# picoclick_c3_v1_1.net
KiCad netlist of a schematic drawn in EAGLE
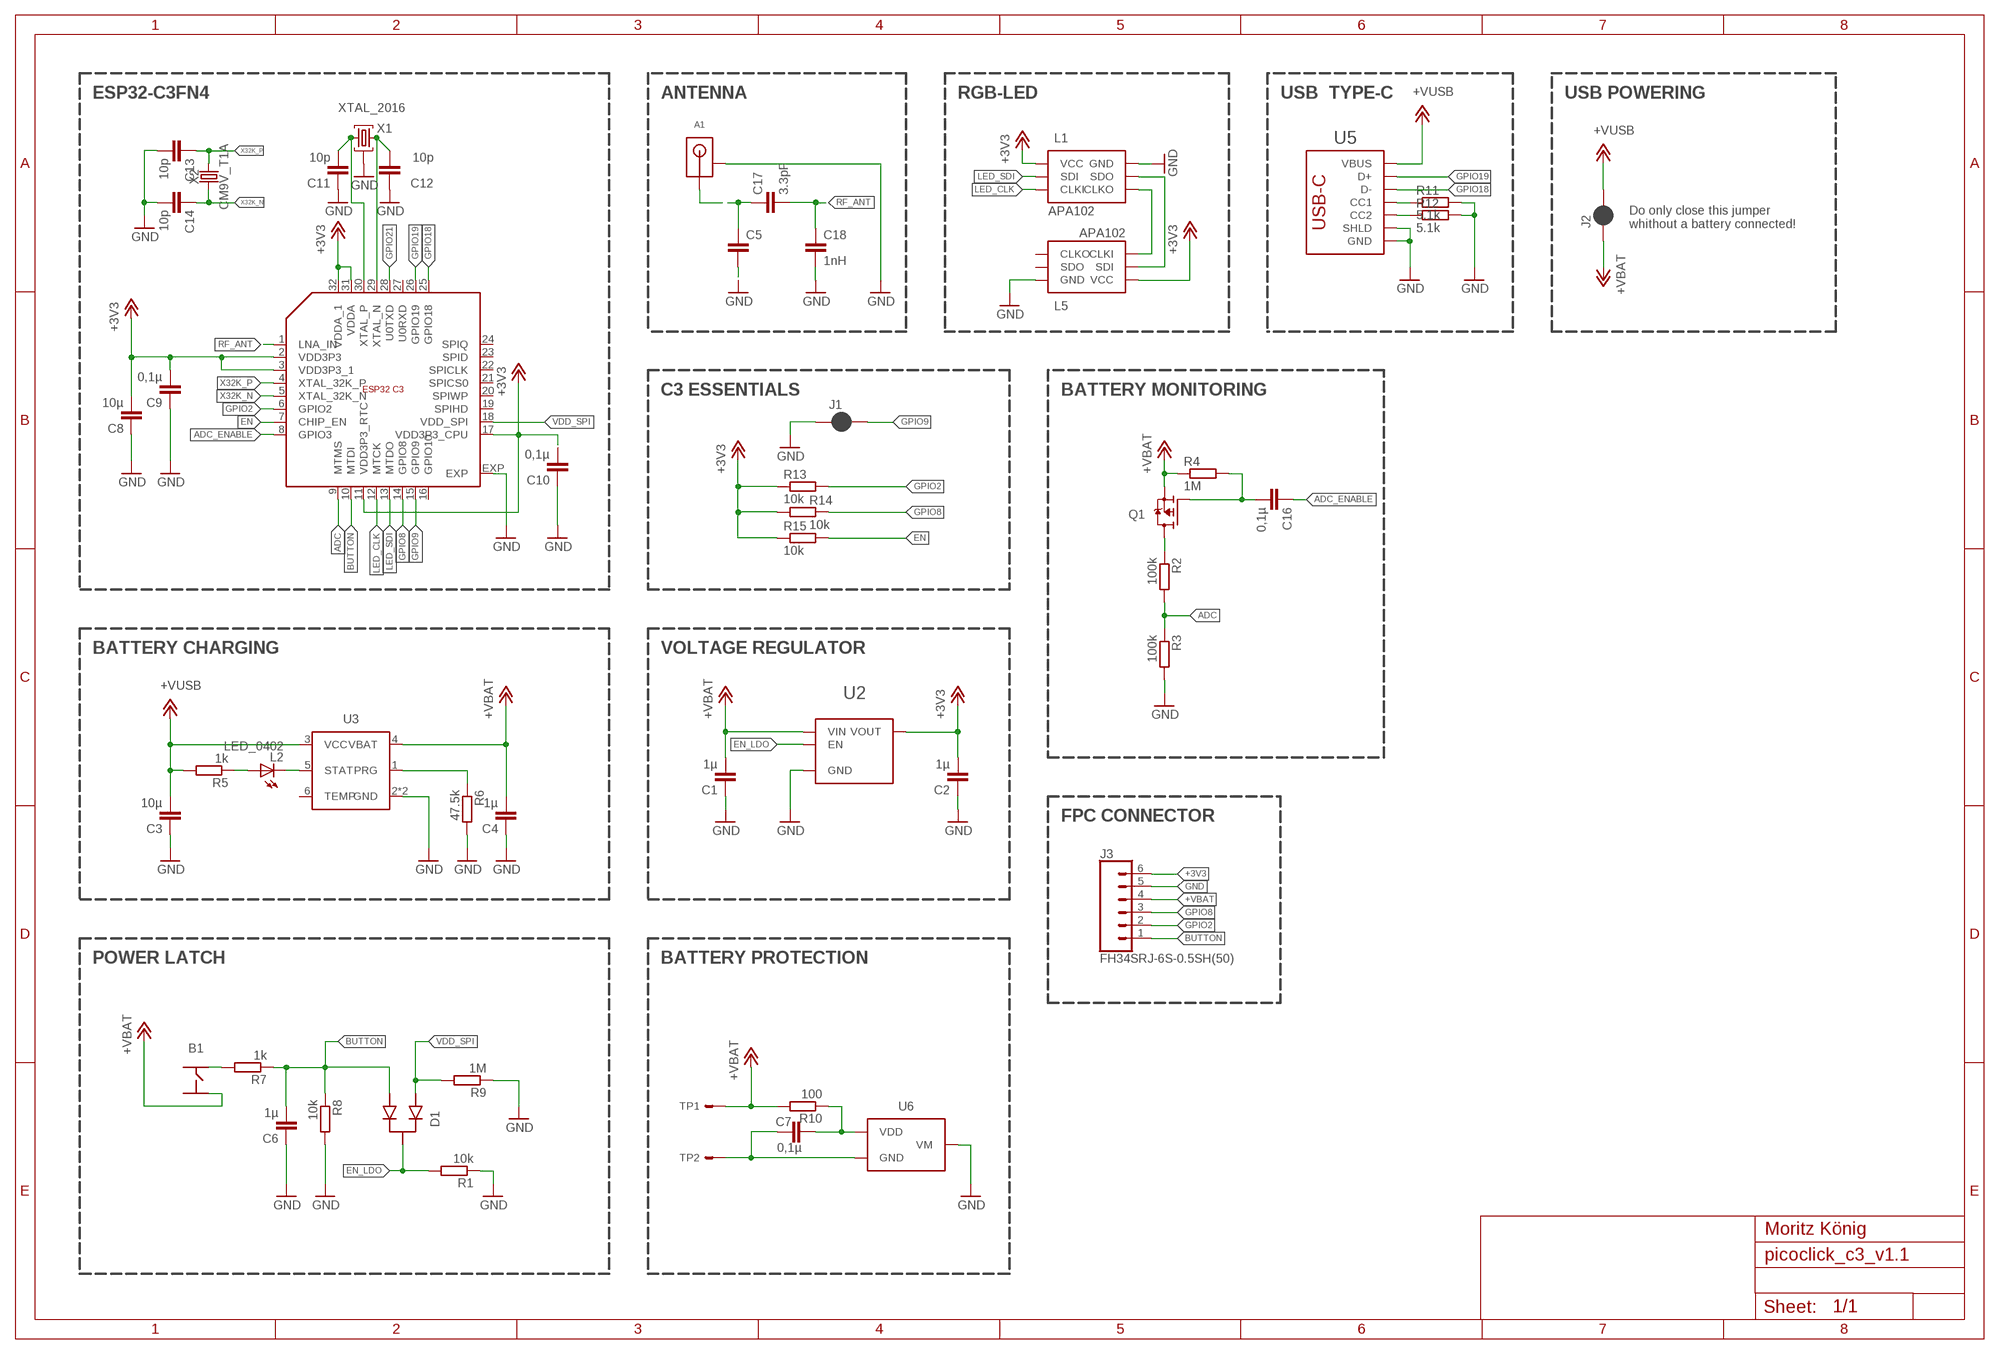
[diagram p0: schematic, sheet 1]

(export (version "E")
  (design (tool "Eeschema 10.0.6"))
  (components
    (comp (ref "A1")
      (value "RFECA3216060A1T_NEW3_M")
      (footprint "eagle-import:RFECA3216060A1T_NEW3_M")
      (libsource (lib "eagle-import") (part "RFECA3216060A1T_NEW3_M"))
    )
    (comp (ref "B1")
      (value "BUTTON_4PIN")
      (footprint "eagle-import:BUTTON_SMD_12MM")
      (libsource (lib "eagle-import") (part "BUTTON_4PIN"))
    )
    (comp (ref "C1")
      (value "1µ")
      (footprint "eagle-import:C0402_S")
      (libsource (lib "eagle-import") (part "C0402_S"))
    )
    (comp (ref "C2")
      (value "1µ")
      (footprint "eagle-import:C0402_S")
      (libsource (lib "eagle-import") (part "C0402_S"))
    )
    (comp (ref "C3")
      (value "10µ")
      (footprint "eagle-import:C0402_S")
      (libsource (lib "eagle-import") (part "C0402_S"))
    )
    (comp (ref "C4")
      (value "1µ")
      (footprint "eagle-import:C0402_S")
      (libsource (lib "eagle-import") (part "C0402_S"))
    )
    (comp (ref "C5")
      (value "C0402_S")
      (footprint "eagle-import:C0402_S")
      (libsource (lib "eagle-import") (part "C0402_S"))
    )
    (comp (ref "C6")
      (value "1µ")
      (footprint "eagle-import:C0402_S")
      (libsource (lib "eagle-import") (part "C0402_S"))
    )
    (comp (ref "C7")
      (value "0,1µ")
      (footprint "eagle-import:C0402_S")
      (libsource (lib "eagle-import") (part "C-EU-0402-WOKEEPOUT_S"))
    )
    (comp (ref "C8")
      (value "10µ")
      (footprint "eagle-import:C0402_S")
      (libsource (lib "eagle-import") (part "C0402_S"))
    )
    (comp (ref "C9")
      (value "0,1µ")
      (footprint "eagle-import:C0402_S")
      (libsource (lib "eagle-import") (part "C0402_S"))
    )
    (comp (ref "C10")
      (value "0,1µ")
      (footprint "eagle-import:C0402_S")
      (libsource (lib "eagle-import") (part "C0402_S"))
    )
    (comp (ref "C11")
      (value "10p")
      (footprint "eagle-import:C0402_S")
      (libsource (lib "eagle-import") (part "C0402_S"))
    )
    (comp (ref "C12")
      (value "10p")
      (footprint "eagle-import:C0402_S")
      (libsource (lib "eagle-import") (part "C0402_S"))
    )
    (comp (ref "C13")
      (value "10p")
      (footprint "eagle-import:C0402_S")
      (libsource (lib "eagle-import") (part "C-EU-0402-WOKEEPOUT_S"))
    )
    (comp (ref "C14")
      (value "10p")
      (footprint "eagle-import:C0402_S")
      (libsource (lib "eagle-import") (part "C-EU-0402-WOKEEPOUT_S"))
    )
    (comp (ref "C16")
      (value "0,1µ")
      (footprint "eagle-import:C0402_S")
      (libsource (lib "eagle-import") (part "C0402_S"))
    )
    (comp (ref "C17")
      (value "3.3pF")
      (footprint "eagle-import:C0402_S")
      (libsource (lib "eagle-import") (part "C0402_S"))
    )
    (comp (ref "C18")
      (value "1nH")
      (footprint "eagle-import:C0402_S")
      (libsource (lib "eagle-import") (part "C0402_S"))
    )
    (comp (ref "D1")
      (value "DAN222")
      (footprint "eagle-import:SOT523")
      (libsource (lib "eagle-import") (part "DAN222"))
    )
    (comp (ref "J1")
      (value "SMT_JUMPER_2_NC_PASTE")
      (footprint "eagle-import:JUMPER_SMALL")
      (libsource (lib "eagle-import") (part "SMT_JUMPER_2_NC_PASTE"))
    )
    (comp (ref "J2")
      (value "JUMPER_SMALL")
      (footprint "eagle-import:JUMPER_SMALL")
      (libsource (lib "eagle-import") (part "JUMPER_SMALL"))
    )
    (comp (ref "J3")
      (value "FH34SRJ-6S-0.5SH(50)")
      (footprint "eagle-import:FH34SRJ-6S-0.5SH(50)")
      (libsource (lib "eagle-import") (part "FH34SRJ-6S-0.5SH(50)"))
    )
    (comp (ref "L1")
      (value "APA102_2020")
      (footprint "eagle-import:APA102_2020")
      (libsource (lib "eagle-import") (part "APA102_2020"))
    )
    (comp (ref "L2")
      (value "LED_0402")
      (footprint "eagle-import:CHIPLED_0402")
      (libsource (lib "eagle-import") (part "LED_0402"))
    )
    (comp (ref "L5")
      (value "APA102_2020")
      (footprint "eagle-import:APA102_2020")
      (libsource (lib "eagle-import") (part "APA102_2020"))
    )
    (comp (ref "Q1")
      (value "WPM2031+SOT1123")
      (footprint "eagle-import:SOT723+1123")
      (libsource (lib "eagle-import") (part "WPM2031+SOT1123"))
    )
    (comp (ref "R1")
      (value "10k")
      (footprint "eagle-import:R0402")
      (libsource (lib "eagle-import") (part "R0402"))
    )
    (comp (ref "R2")
      (value "100k")
      (footprint "eagle-import:R0402")
      (libsource (lib "eagle-import") (part "R0402"))
    )
    (comp (ref "R3")
      (value "100k")
      (footprint "eagle-import:R0402")
      (libsource (lib "eagle-import") (part "R0402"))
    )
    (comp (ref "R4")
      (value "1M")
      (footprint "eagle-import:R0402")
      (libsource (lib "eagle-import") (part "R0402"))
    )
    (comp (ref "R5")
      (value "1k")
      (footprint "eagle-import:R0402")
      (libsource (lib "eagle-import") (part "R0402"))
    )
    (comp (ref "R6")
      (value "47.5k")
      (footprint "eagle-import:R0402")
      (libsource (lib "eagle-import") (part "R0402"))
    )
    (comp (ref "R7")
      (value "1k")
      (footprint "eagle-import:R0402")
      (libsource (lib "eagle-import") (part "R0402"))
    )
    (comp (ref "R8")
      (value "10k")
      (footprint "eagle-import:R0402")
      (libsource (lib "eagle-import") (part "R0402"))
    )
    (comp (ref "R9")
      (value "1M")
      (footprint "eagle-import:R0402")
      (libsource (lib "eagle-import") (part "R0402"))
    )
    (comp (ref "R10")
      (value "100")
      (footprint "eagle-import:R0402")
      (libsource (lib "eagle-import") (part "R-EU-0402-WOKEEPOUT"))
    )
    (comp (ref "R11")
      (value "5.1k")
      (footprint "eagle-import:R0402")
      (libsource (lib "eagle-import") (part "R0402"))
    )
    (comp (ref "R12")
      (value "5.1k")
      (footprint "eagle-import:R0402")
      (libsource (lib "eagle-import") (part "R0402"))
    )
    (comp (ref "R13")
      (value "10k")
      (footprint "eagle-import:R0402")
      (libsource (lib "eagle-import") (part "R0402"))
    )
    (comp (ref "R14")
      (value "10k")
      (footprint "eagle-import:R0402")
      (libsource (lib "eagle-import") (part "R0402"))
    )
    (comp (ref "R15")
      (value "10k")
      (footprint "eagle-import:R0402")
      (libsource (lib "eagle-import") (part "R0402"))
    )
    (comp (ref "TP1")
      (value "TP/SP-1.5X2.0")
      (footprint "eagle-import:SOLDERPAD_1.5X2.0")
      (libsource (lib "eagle-import") (part "TP/SP-1.5X2.0"))
    )
    (comp (ref "TP2")
      (value "TP/SP-1.5X2.0")
      (footprint "eagle-import:SOLDERPAD_1.5X2.0")
      (libsource (lib "eagle-import") (part "TP/SP-1.5X2.0"))
    )
    (comp (ref "U1")
      (value "ESP32_C3_QFN32")
      (footprint "eagle-import:QFN32")
      (libsource (lib "eagle-import") (part "ESP32_C3_QFN32"))
    )
    (comp (ref "U2")
      (value "MIC5504")
      (footprint "eagle-import:TDFN4")
      (libsource (lib "eagle-import") (part "MIC5504"))
    )
    (comp (ref "U3")
      (value "WS4518D")
      (footprint "eagle-import:DFN-6")
      (libsource (lib "eagle-import") (part "WS4518D"))
    )
    (comp (ref "U5")
      (value "USB_C_C393939")
      (footprint "eagle-import:USBC_C393939")
      (libsource (lib "eagle-import") (part "USB_C_C393939"))
    )
    (comp (ref "U6")
      (value "XB6042I2SV")
      (footprint "eagle-import:TDFN4")
      (libsource (lib "eagle-import") (part "XB6042I2SV"))
    )
    (comp (ref "X1")
      (value "XTAL_2016")
      (footprint "eagle-import:XTAL_2016")
      (libsource (lib "eagle-import") (part "XTAL_2016"))
    )
    (comp (ref "X2")
      (value "CM9V_T1A")
      (footprint "eagle-import:XTAL_1016")
      (libsource (lib "eagle-import") (part "CM9V_T1A"))
    )
  )
  (nets
    (net (code "1") (name "+3V3") (class "Default")
      (node (ref "C10") (pin "P$2") (pinfunction "2_P$2") (pintype "passive"))
      (node (ref "C2") (pin "P$2") (pinfunction "2_P$2") (pintype "passive"))
      (node (ref "C8") (pin "P$2") (pinfunction "2_P$2") (pintype "passive"))
      (node (ref "C9") (pin "P$2") (pinfunction "2_P$2") (pintype "passive"))
      (node (ref "J3") (pin "6") (pinfunction "6_6") (pintype "passive"))
      (node (ref "L1") (pin "P1") (pinfunction "VCC_P1") (pintype "bidirectional"))
      (node (ref "L1") (pin "P1.1") (pinfunction "VCC_P1.1") (pintype "bidirectional"))
      (node (ref "L5") (pin "P1") (pinfunction "VCC_P1") (pintype "bidirectional"))
      (node (ref "L5") (pin "P1.1") (pinfunction "VCC_P1.1") (pintype "bidirectional"))
      (node (ref "R13") (pin "1") (pinfunction "1_1") (pintype "passive"))
      (node (ref "R14") (pin "1") (pinfunction "1_1") (pintype "passive"))
      (node (ref "R15") (pin "1") (pinfunction "1_1") (pintype "passive"))
      (node (ref "U1") (pin "11") (pinfunction "VDD3P3_RTC_11") (pintype "bidirectional"))
      (node (ref "U1") (pin "17") (pinfunction "VDD3P3_CPU_17") (pintype "bidirectional"))
      (node (ref "U1") (pin "2") (pinfunction "VDD3P3_2") (pintype "bidirectional"))
      (node (ref "U1") (pin "3") (pinfunction "VDD3P3_1_3") (pintype "bidirectional"))
      (node (ref "U1") (pin "31") (pinfunction "VDDA_31") (pintype "bidirectional"))
      (node (ref "U1") (pin "32") (pinfunction "VDDA_1_32") (pintype "bidirectional"))
      (node (ref "U2") (pin "P1") (pinfunction "VOUT_P1") (pintype "bidirectional"))
    )
    (net (code "2") (name "+VBAT") (class "Default")
      (node (ref "B1") (pin "P4") (pinfunction "4_P4") (pintype "bidirectional"))
      (node (ref "C1") (pin "P$2") (pinfunction "2_P$2") (pintype "passive"))
      (node (ref "C4") (pin "P$2") (pinfunction "2_P$2") (pintype "passive"))
      (node (ref "J2") (pin "P$1") (pinfunction "1_P$1") (pintype "passive"))
      (node (ref "J3") (pin "4") (pinfunction "4_4") (pintype "passive"))
      (node (ref "Q1") (pin "P$2") (pinfunction "S_P$2") (pintype "passive"))
      (node (ref "R10") (pin "2") (pinfunction "2_2") (pintype "passive"))
      (node (ref "R4") (pin "1") (pinfunction "1_1") (pintype "passive"))
      (node (ref "TP1") (pin "1") (pinfunction "S_1") (pintype "passive"))
      (node (ref "U2") (pin "P4") (pinfunction "VIN_P4") (pintype "bidirectional"))
      (node (ref "U3") (pin "4") (pinfunction "VBAT_4") (pintype "bidirectional"))
    )
    (net (code "3") (name "+VUSB") (class "Default")
      (node (ref "C3") (pin "P$2") (pinfunction "2_P$2") (pintype "passive"))
      (node (ref "J2") (pin "P$2") (pinfunction "2_P$2") (pintype "passive"))
      (node (ref "R5") (pin "2") (pinfunction "2_2") (pintype "passive"))
      (node (ref "U3") (pin "3") (pinfunction "VCC_3") (pintype "bidirectional"))
      (node (ref "U5") (pin "A4B9") (pinfunction "VBUS_A4B9") (pintype "bidirectional"))
      (node (ref "U5") (pin "B4A9") (pinfunction "VBUS_B4A9") (pintype "bidirectional"))
    )
    (net (code "4") (name "ADC") (class "Default")
      (node (ref "R2") (pin "2") (pinfunction "2_2") (pintype "passive"))
      (node (ref "R3") (pin "1") (pinfunction "1_1") (pintype "passive"))
      (node (ref "U1") (pin "9") (pinfunction "MTMS_9") (pintype "bidirectional"))
    )
    (net (code "5") (name "ADC_ENABLE") (class "Default")
      (node (ref "C16") (pin "P$1") (pinfunction "1_P$1") (pintype "passive"))
      (node (ref "U1") (pin "8") (pinfunction "GPIO3_8") (pintype "bidirectional"))
    )
    (net (code "6") (name "BUTTON") (class "Default")
      (node (ref "C6") (pin "P$2") (pinfunction "2_P$2") (pintype "passive"))
      (node (ref "D1") (pin "2") (pinfunction "2_2") (pintype "bidirectional"))
      (node (ref "J3") (pin "1") (pinfunction "1_1") (pintype "passive"))
      (node (ref "R7") (pin "1") (pinfunction "1_1") (pintype "passive"))
      (node (ref "R8") (pin "1") (pinfunction "1_1") (pintype "passive"))
      (node (ref "U1") (pin "10") (pinfunction "MTDI_10") (pintype "bidirectional"))
    )
    (net (code "7") (name "EN") (class "Default")
      (node (ref "R15") (pin "2") (pinfunction "2_2") (pintype "passive"))
      (node (ref "U1") (pin "7") (pinfunction "CHIP_EN_7") (pintype "bidirectional"))
    )
    (net (code "8") (name "EN_LDO") (class "Default")
      (node (ref "D1") (pin "3") (pinfunction "3_3") (pintype "bidirectional"))
      (node (ref "R1") (pin "2") (pinfunction "2_2") (pintype "passive"))
      (node (ref "U2") (pin "P3") (pinfunction "EN_P3") (pintype "bidirectional"))
    )
    (net (code "9") (name "GND") (class "Default")
      (node (ref "A1") (pin "PGND1") (pinfunction "GND_PGND1") (pintype "bidirectional"))
      (node (ref "A1") (pin "PGND2") (pinfunction "GND_PGND2") (pintype "bidirectional"))
      (node (ref "C1") (pin "P$1") (pinfunction "1_P$1") (pintype "passive"))
      (node (ref "C10") (pin "P$1") (pinfunction "1_P$1") (pintype "passive"))
      (node (ref "C11") (pin "P$1") (pinfunction "1_P$1") (pintype "passive"))
      (node (ref "C12") (pin "P$1") (pinfunction "1_P$1") (pintype "passive"))
      (node (ref "C13") (pin "P$2") (pinfunction "2_P$2") (pintype "passive"))
      (node (ref "C14") (pin "P$2") (pinfunction "2_P$2") (pintype "passive"))
      (node (ref "C18") (pin "P$2") (pinfunction "2_P$2") (pintype "passive"))
      (node (ref "C2") (pin "P$1") (pinfunction "1_P$1") (pintype "passive"))
      (node (ref "C3") (pin "P$1") (pinfunction "1_P$1") (pintype "passive"))
      (node (ref "C4") (pin "P$1") (pinfunction "1_P$1") (pintype "passive"))
      (node (ref "C5") (pin "P$2") (pinfunction "2_P$2") (pintype "passive"))
      (node (ref "C6") (pin "P$1") (pinfunction "1_P$1") (pintype "passive"))
      (node (ref "C8") (pin "P$1") (pinfunction "1_P$1") (pintype "passive"))
      (node (ref "C9") (pin "P$1") (pinfunction "1_P$1") (pintype "passive"))
      (node (ref "J1") (pin "P$1") (pinfunction "1_P$1") (pintype "passive"))
      (node (ref "J3") (pin "5") (pinfunction "5_5") (pintype "passive"))
      (node (ref "L1") (pin "P6") (pinfunction "GND_P6") (pintype "bidirectional"))
      (node (ref "L1") (pin "P6.1") (pinfunction "GND_P6.1") (pintype "bidirectional"))
      (node (ref "L5") (pin "P6") (pinfunction "GND_P6") (pintype "bidirectional"))
      (node (ref "L5") (pin "P6.1") (pinfunction "GND_P6.1") (pintype "bidirectional"))
      (node (ref "R1") (pin "1") (pinfunction "1_1") (pintype "passive"))
      (node (ref "R11") (pin "2") (pinfunction "2_2") (pintype "passive"))
      (node (ref "R12") (pin "2") (pinfunction "2_2") (pintype "passive"))
      (node (ref "R3") (pin "2") (pinfunction "2_2") (pintype "passive"))
      (node (ref "R6") (pin "2") (pinfunction "2_2") (pintype "passive"))
      (node (ref "R8") (pin "2") (pinfunction "2_2") (pintype "passive"))
      (node (ref "R9") (pin "1") (pinfunction "1_1") (pintype "passive"))
      (node (ref "U1") (pin "EXP") (pinfunction "EXP_EXP") (pintype "bidirectional"))
      (node (ref "U2") (pin "EXP") (pinfunction "GND_EXP") (pintype "bidirectional"))
      (node (ref "U2") (pin "P2") (pinfunction "GND_P2") (pintype "bidirectional"))
      (node (ref "U3") (pin "2") (pinfunction "GND_2") (pintype "bidirectional"))
      (node (ref "U3") (pin "EXP") (pinfunction "GND_EXP") (pintype "bidirectional"))
      (node (ref "U5") (pin "A1B12") (pinfunction "GND_A1B12") (pintype "bidirectional"))
      (node (ref "U5") (pin "B1A12") (pinfunction "GND_B1A12") (pintype "bidirectional"))
      (node (ref "U5") (pin "S1") (pinfunction "SHLD_S1") (pintype "bidirectional"))
      (node (ref "U5") (pin "S2") (pinfunction "SHLD_S2") (pintype "bidirectional"))
      (node (ref "U5") (pin "S3") (pinfunction "SHLD_S3") (pintype "bidirectional"))
      (node (ref "U5") (pin "S4") (pinfunction "SHLD_S4") (pintype "bidirectional"))
      (node (ref "U6") (pin "P4") (pinfunction "VM_P4") (pintype "bidirectional"))
      (node (ref "X1") (pin "P2") (pinfunction "G_P2") (pintype "passive"))
      (node (ref "X1") (pin "P4") (pinfunction "G_P4") (pintype "passive"))
    )
    (net (code "10") (name "GPIO2") (class "Default")
      (node (ref "J3") (pin "2") (pinfunction "2_2") (pintype "passive"))
      (node (ref "R13") (pin "2") (pinfunction "2_2") (pintype "passive"))
      (node (ref "U1") (pin "6") (pinfunction "GPIO2_6") (pintype "bidirectional"))
    )
    (net (code "11") (name "GPIO8") (class "Default")
      (node (ref "J3") (pin "3") (pinfunction "3_3") (pintype "passive"))
      (node (ref "R14") (pin "2") (pinfunction "2_2") (pintype "passive"))
      (node (ref "U1") (pin "14") (pinfunction "GPIO8_14") (pintype "bidirectional"))
    )
    (net (code "12") (name "GPIO9") (class "Default")
      (node (ref "J1") (pin "P$2") (pinfunction "2_P$2") (pintype "passive"))
      (node (ref "U1") (pin "15") (pinfunction "GPIO9_15") (pintype "bidirectional"))
    )
    (net (code "13") (name "GPIO18") (class "Default")
      (node (ref "U1") (pin "25") (pinfunction "GPIO18_25") (pintype "bidirectional"))
      (node (ref "U5") (pin "A7") (pinfunction "D-_A7") (pintype "bidirectional"))
      (node (ref "U5") (pin "B7") (pinfunction "D-_B7") (pintype "bidirectional"))
    )
    (net (code "14") (name "GPIO19") (class "Default")
      (node (ref "U1") (pin "26") (pinfunction "GPIO19_26") (pintype "bidirectional"))
      (node (ref "U5") (pin "A6") (pinfunction "D+_A6") (pintype "bidirectional"))
      (node (ref "U5") (pin "B6") (pinfunction "D+_B6") (pintype "bidirectional"))
    )
    (net (code "15") (name "GPIO21") (class "Default")
      (node (ref "U1") (pin "28") (pinfunction "U0TXD_28") (pintype "bidirectional"))
    )
    (net (code "16") (name "LED_CLK") (class "Default")
      (node (ref "L1") (pin "P5") (pinfunction "CLKI_P5") (pintype "bidirectional"))
      (node (ref "U1") (pin "12") (pinfunction "MTCK_12") (pintype "bidirectional"))
    )
    (net (code "17") (name "LED_SDI") (class "Default")
      (node (ref "L1") (pin "P4") (pinfunction "SDI_P4") (pintype "bidirectional"))
      (node (ref "U1") (pin "13") (pinfunction "MTDO_13") (pintype "bidirectional"))
    )
    (net (code "18") (name "Net-(A1-ANT)") (class "Default")
      (node (ref "A1") (pin "PFEED") (pinfunction "ANT_PFEED") (pintype "bidirectional"))
      (node (ref "C17") (pin "P$1") (pinfunction "1_P$1") (pintype "passive"))
      (node (ref "C5") (pin "P$1") (pinfunction "1_P$1") (pintype "passive"))
    )
    (net (code "19") (name "Net-(B1-2)") (class "Default")
      (node (ref "B1") (pin "P2") (pinfunction "2_P2") (pintype "bidirectional"))
      (node (ref "R7") (pin "2") (pinfunction "2_2") (pintype "passive"))
    )
    (net (code "20") (name "Net-(C7-1)") (class "Default")
      (node (ref "C7") (pin "P$1") (pinfunction "1_P$1") (pintype "passive"))
      (node (ref "TP2") (pin "1") (pinfunction "S_1") (pintype "passive"))
      (node (ref "U6") (pin "EXP") (pinfunction "GND_EXP") (pintype "bidirectional"))
      (node (ref "U6") (pin "P2") (pinfunction "GND_P2") (pintype "bidirectional"))
      (node (ref "U6") (pin "P3") (pinfunction "GND_P3") (pintype "bidirectional"))
    )
    (net (code "21") (name "Net-(C7-2)") (class "Default")
      (node (ref "C7") (pin "P$2") (pinfunction "2_P$2") (pintype "passive"))
      (node (ref "R10") (pin "1") (pinfunction "1_1") (pintype "passive"))
      (node (ref "U6") (pin "P1") (pinfunction "VDD_P1") (pintype "bidirectional"))
    )
    (net (code "22") (name "Net-(C11-2)") (class "Default")
      (node (ref "C11") (pin "P$2") (pinfunction "2_P$2") (pintype "passive"))
      (node (ref "U1") (pin "30") (pinfunction "XTAL_P_30") (pintype "bidirectional"))
      (node (ref "X1") (pin "P1") (pinfunction "1_P1") (pintype "passive"))
    )
    (net (code "23") (name "Net-(C12-2)") (class "Default")
      (node (ref "C12") (pin "P$2") (pinfunction "2_P$2") (pintype "passive"))
      (node (ref "U1") (pin "29") (pinfunction "XTAL_N_29") (pintype "bidirectional"))
      (node (ref "X1") (pin "P3") (pinfunction "2_P3") (pintype "passive"))
    )
    (net (code "24") (name "Net-(C16-2)") (class "Default")
      (node (ref "C16") (pin "P$2") (pinfunction "2_P$2") (pintype "passive"))
      (node (ref "Q1") (pin "P$1") (pinfunction "G_P$1") (pintype "passive"))
      (node (ref "R4") (pin "2") (pinfunction "2_2") (pintype "passive"))
    )
    (net (code "25") (name "Net-(L1-CLKO)") (class "Default")
      (node (ref "L1") (pin "P2") (pinfunction "CLKO_P2") (pintype "bidirectional"))
      (node (ref "L5") (pin "P5") (pinfunction "CLKI_P5") (pintype "bidirectional"))
    )
    (net (code "26") (name "Net-(L1-SDO)") (class "Default")
      (node (ref "L1") (pin "P3") (pinfunction "SDO_P3") (pintype "bidirectional"))
      (node (ref "L5") (pin "P4") (pinfunction "SDI_P4") (pintype "bidirectional"))
    )
    (net (code "27") (name "Net-(L2-A)") (class "Default")
      (node (ref "L2") (pin "P$2") (pinfunction "A_P$2") (pintype "passive"))
      (node (ref "R5") (pin "1") (pinfunction "1_1") (pintype "passive"))
    )
    (net (code "28") (name "Net-(L2-C)") (class "Default")
      (node (ref "L2") (pin "P$1") (pinfunction "C_P$1") (pintype "passive"))
      (node (ref "U3") (pin "5") (pinfunction "STAT_5") (pintype "bidirectional"))
    )
    (net (code "29") (name "Net-(Q1-D)") (class "Default")
      (node (ref "Q1") (pin "P$3") (pinfunction "D_P$3") (pintype "passive"))
      (node (ref "R2") (pin "1") (pinfunction "1_1") (pintype "passive"))
    )
    (net (code "30") (name "Net-(U3-PRG)") (class "Default")
      (node (ref "R6") (pin "1") (pinfunction "1_1") (pintype "passive"))
      (node (ref "U3") (pin "1") (pinfunction "PRG_1") (pintype "bidirectional"))
    )
    (net (code "31") (name "Net-(U5-CC1)") (class "Default")
      (node (ref "R11") (pin "1") (pinfunction "1_1") (pintype "passive"))
      (node (ref "U5") (pin "A5") (pinfunction "CC1_A5") (pintype "bidirectional"))
    )
    (net (code "32") (name "Net-(U5-CC2)") (class "Default")
      (node (ref "R12") (pin "1") (pinfunction "1_1") (pintype "passive"))
      (node (ref "U5") (pin "B5") (pinfunction "CC2_B5") (pintype "bidirectional"))
    )
    (net (code "33") (name "RF_ANT") (class "Default")
      (node (ref "C17") (pin "P$2") (pinfunction "2_P$2") (pintype "passive"))
      (node (ref "C18") (pin "P$1") (pinfunction "1_P$1") (pintype "passive"))
      (node (ref "U1") (pin "1") (pinfunction "LNA_IN_1") (pintype "bidirectional"))
    )
    (net (code "34") (name "VDD_SPI") (class "Default")
      (node (ref "D1") (pin "1") (pinfunction "1_1") (pintype "bidirectional"))
      (node (ref "R9") (pin "2") (pinfunction "2_2") (pintype "passive"))
      (node (ref "U1") (pin "18") (pinfunction "VDD_SPI_18") (pintype "bidirectional"))
    )
    (net (code "35") (name "X32K_N") (class "Default")
      (node (ref "C14") (pin "P$1") (pinfunction "1_P$1") (pintype "passive"))
      (node (ref "U1") (pin "5") (pinfunction "XTAL_32K_N_5") (pintype "bidirectional"))
      (node (ref "X2") (pin "P$1") (pinfunction "1_P$1") (pintype "passive"))
    )
    (net (code "36") (name "X32K_P") (class "Default")
      (node (ref "C13") (pin "P$1") (pinfunction "1_P$1") (pintype "passive"))
      (node (ref "U1") (pin "4") (pinfunction "XTAL_32K_P_4") (pintype "bidirectional"))
      (node (ref "X2") (pin "P$2") (pinfunction "2_P$2") (pintype "passive"))
    )
    (net (code "37") (name "unconnected-(B1-1-PadP1)") (class "Default")
      (node (ref "B1") (pin "P1") (pinfunction "1_P1") (pintype "bidirectional"))
    )
    (net (code "38") (name "unconnected-(B1-3-PadP3)") (class "Default")
      (node (ref "B1") (pin "P3") (pinfunction "3_P3") (pintype "bidirectional"))
    )
    (net (code "39") (name "unconnected-(L5-CLKO-PadP2)") (class "Default")
      (node (ref "L5") (pin "P2") (pinfunction "CLKO_P2") (pintype "bidirectional"))
    )
    (net (code "40") (name "unconnected-(L5-SDO-PadP3)") (class "Default")
      (node (ref "L5") (pin "P3") (pinfunction "SDO_P3") (pintype "bidirectional"))
    )
    (net (code "41") (name "unconnected-(U1-GPIO10-Pad16)") (class "Default")
      (node (ref "U1") (pin "16") (pinfunction "GPIO10_16") (pintype "bidirectional"))
    )
    (net (code "42") (name "unconnected-(U1-SPICLK-Pad22)") (class "Default")
      (node (ref "U1") (pin "22") (pinfunction "SPICLK_22") (pintype "bidirectional"))
    )
    (net (code "43") (name "unconnected-(U1-SPICS0-Pad21)") (class "Default")
      (node (ref "U1") (pin "21") (pinfunction "SPICS0_21") (pintype "bidirectional"))
    )
    (net (code "44") (name "unconnected-(U1-SPID-Pad23)") (class "Default")
      (node (ref "U1") (pin "23") (pinfunction "SPID_23") (pintype "bidirectional"))
    )
    (net (code "45") (name "unconnected-(U1-SPIHD-Pad19)") (class "Default")
      (node (ref "U1") (pin "19") (pinfunction "SPIHD_19") (pintype "bidirectional"))
    )
    (net (code "46") (name "unconnected-(U1-SPIQ-Pad24)") (class "Default")
      (node (ref "U1") (pin "24") (pinfunction "SPIQ_24") (pintype "bidirectional"))
    )
    (net (code "47") (name "unconnected-(U1-SPIWP-Pad20)") (class "Default")
      (node (ref "U1") (pin "20") (pinfunction "SPIWP_20") (pintype "bidirectional"))
    )
    (net (code "48") (name "unconnected-(U1-U0RXD-Pad27)") (class "Default")
      (node (ref "U1") (pin "27") (pinfunction "U0RXD_27") (pintype "bidirectional"))
    )
    (net (code "49") (name "unconnected-(U3-TEMP-Pad6)") (class "Default")
      (node (ref "U3") (pin "6") (pinfunction "TEMP_6") (pintype "bidirectional"))
    )
  )
)
